# OpenPLCv0_2_0_ExpansionHeader.net
KiCad netlist of a schematic drawn in Altium Designer
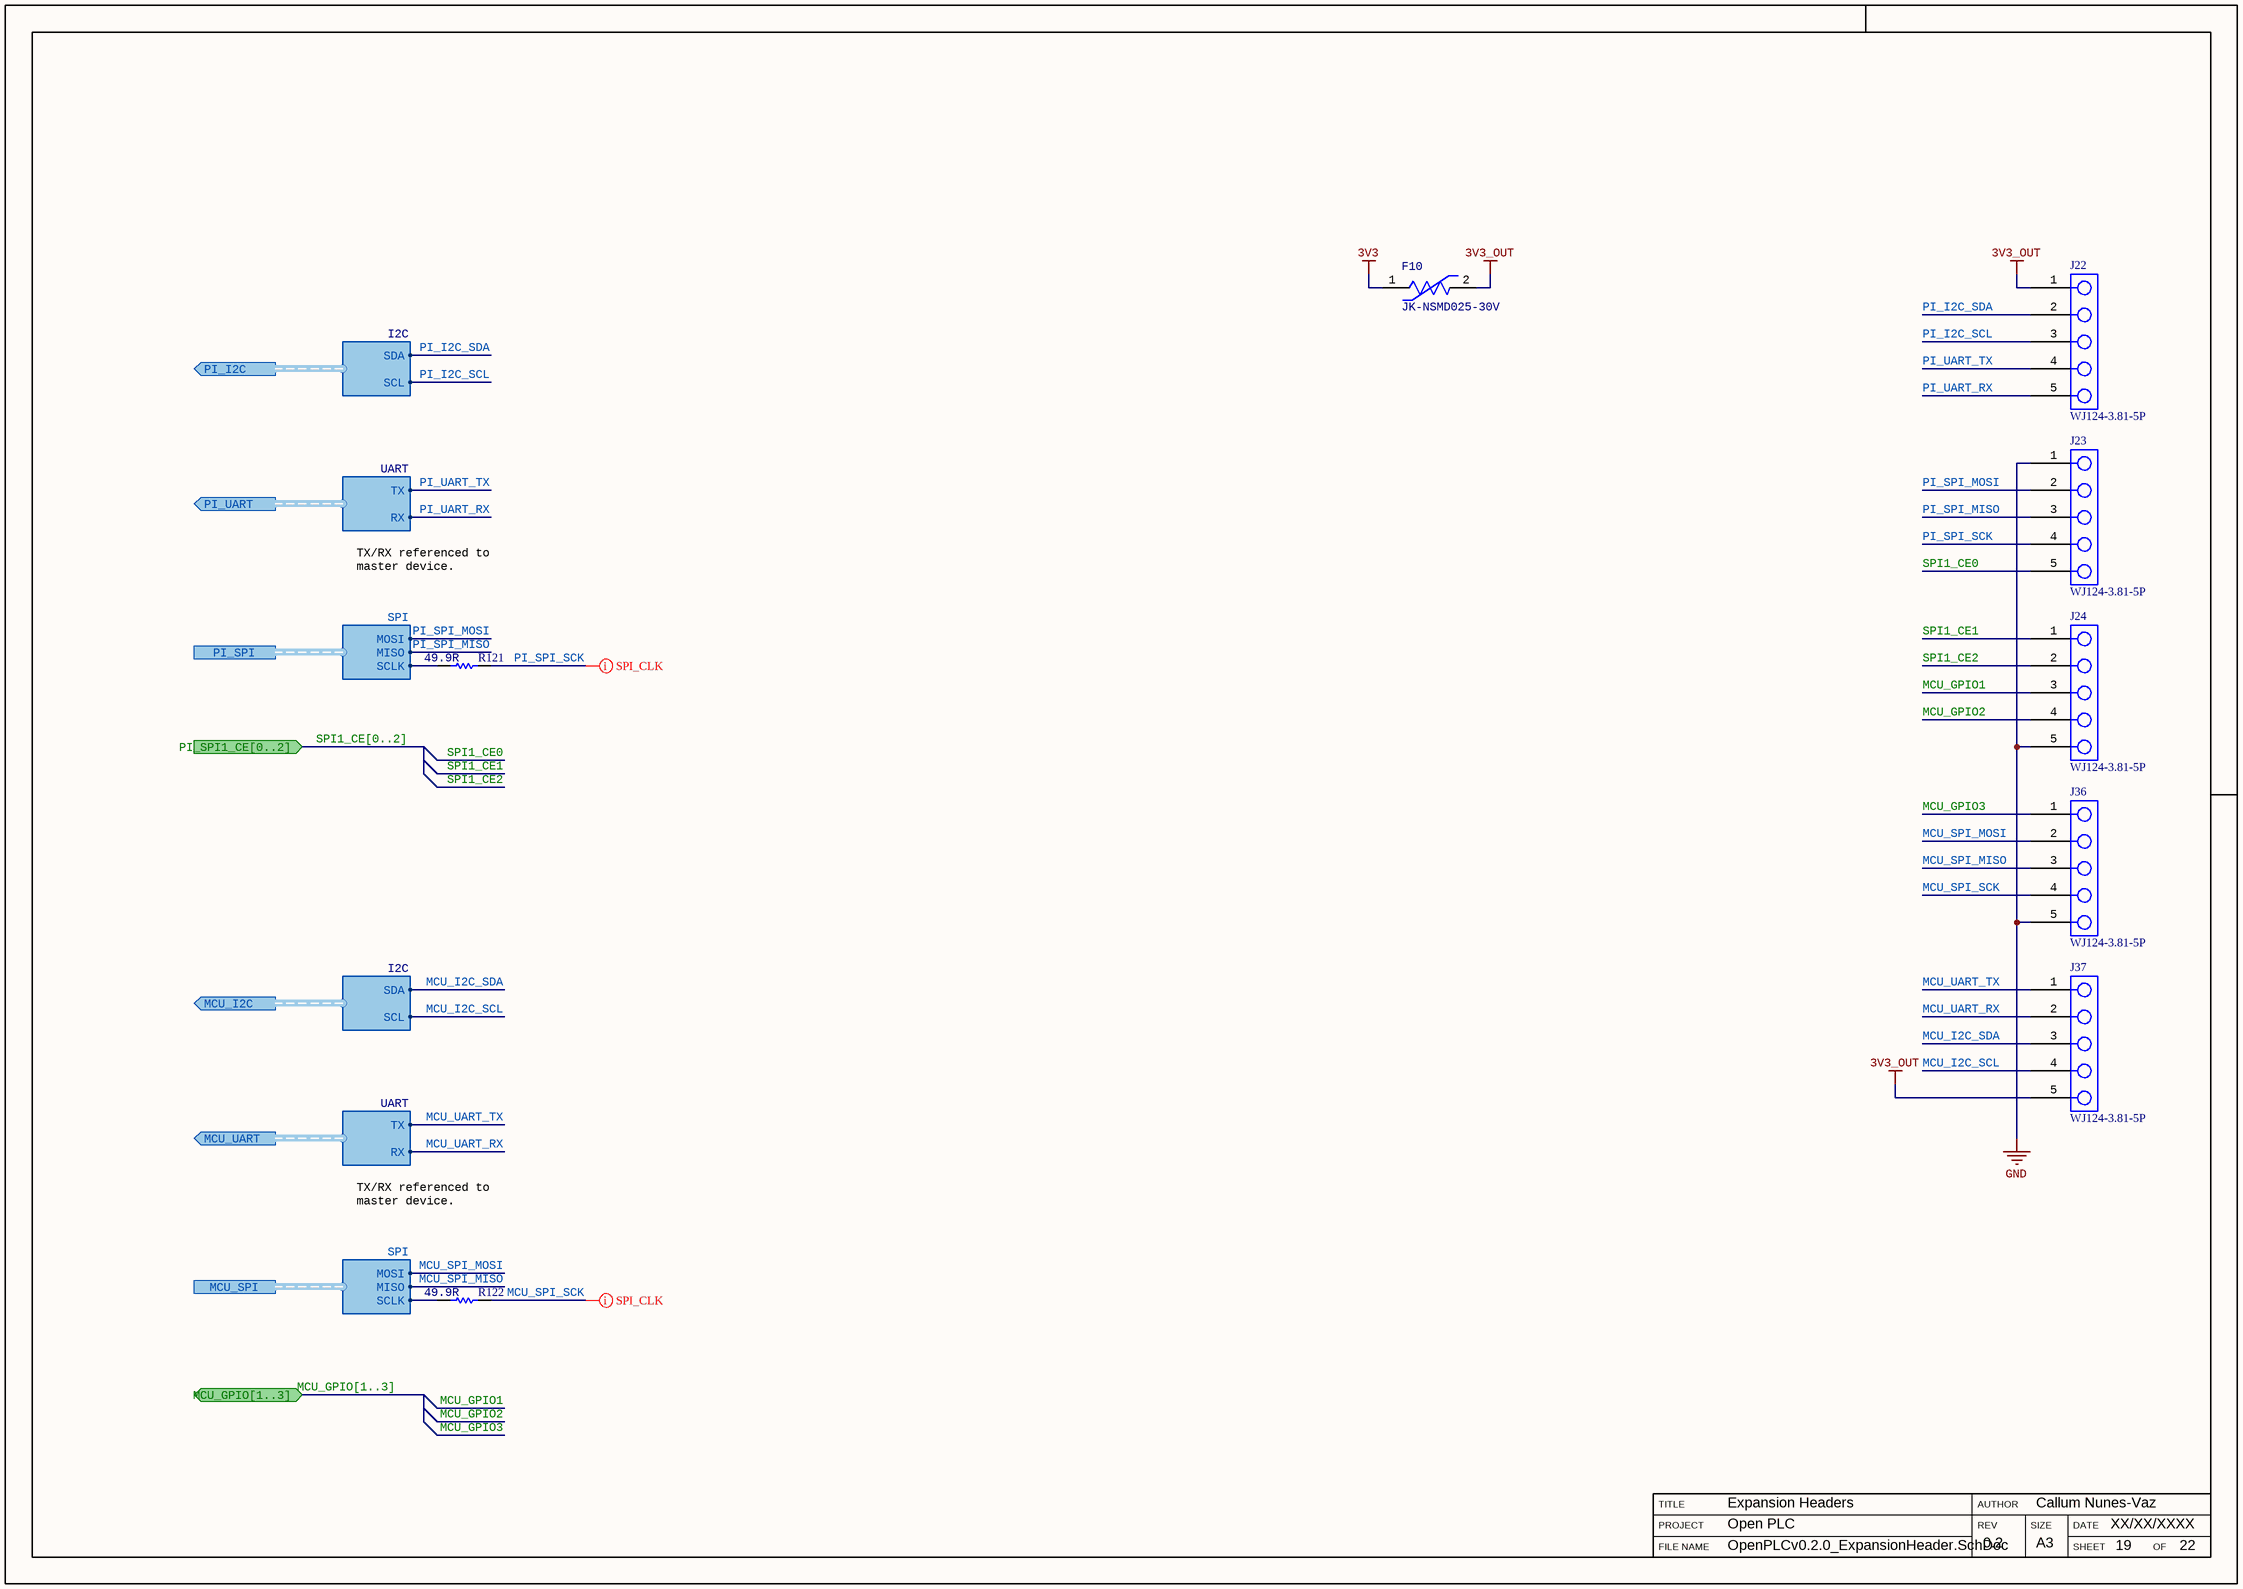
[diagram p0: OpenPLCv0.2.0_ExpansionHeader.SchDoc]

(export (version "E")
  (design (tool "Eeschema 10.0.6"))
  (components
    (comp (ref "F10")
      (value "JK-NSMD025-30V")
      (footprint "SMD_RES_1206(3216)_N")
      (description "Polymeric 30V 500mA 0.08s 700mΩ 1206 PTC Resettable Fuses RoHS")
      (libsource (lib "BrauV2_Resistor") (part "JK-NSMD025-30V"))
    )
    (comp (ref "J22")
      (value "WJ124-3.81-5P")
      (footprint "WJ124-3.81-5P_BoardEdgeAlt")
      (description "5 Wiring Board - Line to Board 0.150\"(3.81mm) 5 1 P=3.81mm Screw terminal ROHS")
      (libsource (lib "OpenPLCv0.2.0_Connector") (part "WJ124-3.81-5P"))
    )
    (comp (ref "J23")
      (value "WJ124-3.81-5P")
      (footprint "WJ124-3.81-5P_BoardEdgeAlt")
      (description "5 Wiring Board - Line to Board 0.150\"(3.81mm) 5 1 P=3.81mm Screw terminal ROHS")
      (libsource (lib "OpenPLCv0.2.0_Connector") (part "WJ124-3.81-5P"))
    )
    (comp (ref "J24")
      (value "WJ124-3.81-5P")
      (footprint "WJ124-3.81-5P_BoardEdgeAlt")
      (description "5 Wiring Board - Line to Board 0.150\"(3.81mm) 5 1 P=3.81mm Screw terminal ROHS")
      (libsource (lib "OpenPLCv0.2.0_Connector") (part "WJ124-3.81-5P"))
    )
    (comp (ref "J36")
      (value "WJ124-3.81-5P")
      (footprint "WJ124-3.81-5P_BoardEdgeAlt")
      (description "5 Wiring Board - Line to Board 0.150\"(3.81mm) 5 1 P=3.81mm Screw terminal ROHS")
      (libsource (lib "OpenPLCv0.2.0_Connector") (part "WJ124-3.81-5P"))
    )
    (comp (ref "J37")
      (value "WJ124-3.81-5P")
      (footprint "WJ124-3.81-5P_BoardEdgeAlt")
      (description "5 Wiring Board - Line to Board 0.150\"(3.81mm) 5 1 P=3.81mm Screw terminal ROHS")
      (libsource (lib "OpenPLCv0.2.0_Connector") (part "WJ124-3.81-5P"))
    )
    (comp (ref "R121")
      (value "RC0402FR-0749R9L")
      (footprint "SMD_RES_0402(1005)_N")
      (description "49.9Ω ±1% 1/16W ±100ppm/℃ 0402 Chip Resistor - Surface Mount RoHS")
      (fields (field (name "TOLERANCE") "1%") (field (name "RESISTANCE") "49.9R"))
      (libsource (lib "OpenPLCv0.2.0_Resistor") (part "49R9 0402 1% 1/16W"))
    )
    (comp (ref "R122")
      (value "RC0402FR-0749R9L")
      (footprint "SMD_RES_0402(1005)_N")
      (description "49.9Ω ±1% 1/16W ±100ppm/℃ 0402 Chip Resistor - Surface Mount RoHS")
      (fields (field (name "TOLERANCE") "1%") (field (name "RESISTANCE") "49.9R"))
      (libsource (lib "OpenPLCv0.2.0_Resistor") (part "49R9 0402 1% 1/16W"))
    )
  )
  (nets
    (net (code "4") (name "/MCU_GPIO1") (class "Default")
      (node (ref "J24") (pin "3") (pinfunction "3_3") (pintype "passive"))
    )
    (net (code "5") (name "/MCU_GPIO2") (class "Default")
      (node (ref "J24") (pin "4") (pinfunction "4_4") (pintype "passive"))
    )
    (net (code "6") (name "/MCU_GPIO3") (class "Default")
      (node (ref "J36") (pin "1") (pinfunction "1_1") (pintype "passive"))
    )
    (net (code "8") (name "/MCU_I2C_SCL") (class "Default")
      (node (ref "J37") (pin "4") (pinfunction "4_4") (pintype "passive"))
    )
    (net (code "9") (name "/MCU_I2C_SDA") (class "Default")
      (node (ref "J37") (pin "3") (pinfunction "3_3") (pintype "passive"))
    )
    (net (code "10") (name "/MCU_SPI_MISO") (class "Default")
      (node (ref "J36") (pin "3") (pinfunction "3_3") (pintype "passive"))
    )
    (net (code "11") (name "/MCU_SPI_MOSI") (class "Default")
      (node (ref "J36") (pin "2") (pinfunction "2_2") (pintype "passive"))
    )
    (net (code "12") (name "/MCU_SPI_SCK") (class "Default")
      (node (ref "J36") (pin "4") (pinfunction "4_4") (pintype "passive"))
      (node (ref "R122") (pin "2") (pinfunction "2_2") (pintype "passive"))
    )
    (net (code "13") (name "/MCU_UART_RX") (class "Default")
      (node (ref "J37") (pin "2") (pinfunction "2_2") (pintype "passive"))
    )
    (net (code "14") (name "/MCU_UART_TX") (class "Default")
      (node (ref "J37") (pin "1") (pinfunction "1_1") (pintype "passive"))
    )
    (net (code "15") (name "/PI_I2C_SCL") (class "Default")
      (node (ref "J22") (pin "3") (pinfunction "3_3") (pintype "passive"))
    )
    (net (code "16") (name "/PI_I2C_SDA") (class "Default")
      (node (ref "J22") (pin "2") (pinfunction "2_2") (pintype "passive"))
    )
    (net (code "17") (name "/PI_SPI_MISO") (class "Default")
      (node (ref "J23") (pin "3") (pinfunction "3_3") (pintype "passive"))
    )
    (net (code "18") (name "/PI_SPI_MOSI") (class "Default")
      (node (ref "J23") (pin "2") (pinfunction "2_2") (pintype "passive"))
    )
    (net (code "19") (name "/PI_SPI_SCK") (class "Default")
      (node (ref "J23") (pin "4") (pinfunction "4_4") (pintype "passive"))
      (node (ref "R121") (pin "2") (pinfunction "2_2") (pintype "passive"))
    )
    (net (code "20") (name "/PI_UART_RX") (class "Default")
      (node (ref "J22") (pin "5") (pinfunction "5_5") (pintype "passive"))
    )
    (net (code "21") (name "/PI_UART_TX") (class "Default")
      (node (ref "J22") (pin "4") (pinfunction "4_4") (pintype "passive"))
    )
    (net (code "22") (name "/SPI1_CE0") (class "Default")
      (node (ref "J23") (pin "5") (pinfunction "5_5") (pintype "passive"))
    )
    (net (code "23") (name "/SPI1_CE1") (class "Default")
      (node (ref "J24") (pin "1") (pinfunction "1_1") (pintype "passive"))
    )
    (net (code "24") (name "/SPI1_CE2") (class "Default")
      (node (ref "J24") (pin "2") (pinfunction "2_2") (pintype "passive"))
    )
    (net (code "29") (name "3V3") (class "Default")
      (node (ref "F10") (pin "1") (pinfunction "1_1") (pintype "passive"))
    )
    (net (code "30") (name "3V3_OUT") (class "Default")
      (node (ref "F10") (pin "2") (pinfunction "2_2") (pintype "passive"))
      (node (ref "J22") (pin "1") (pinfunction "1_1") (pintype "passive"))
      (node (ref "J37") (pin "5") (pinfunction "5_5") (pintype "passive"))
    )
    (net (code "31") (name "GND") (class "Default")
      (node (ref "J23") (pin "1") (pinfunction "1_1") (pintype "passive"))
      (node (ref "J24") (pin "5") (pinfunction "5_5") (pintype "passive"))
      (node (ref "J36") (pin "5") (pinfunction "5_5") (pintype "passive"))
    )
    (net (code "32") (name "unconnected-(R121-Pad1)") (class "Default")
      (node (ref "R121") (pin "1") (pinfunction "1_1") (pintype "passive"))
    )
    (net (code "33") (name "unconnected-(R122-Pad1)") (class "Default")
      (node (ref "R122") (pin "1") (pinfunction "1_1") (pintype "passive"))
    )
  )
)
